# high_side_switch.net
KiCad netlist of a schematic drawn in Altium Designer
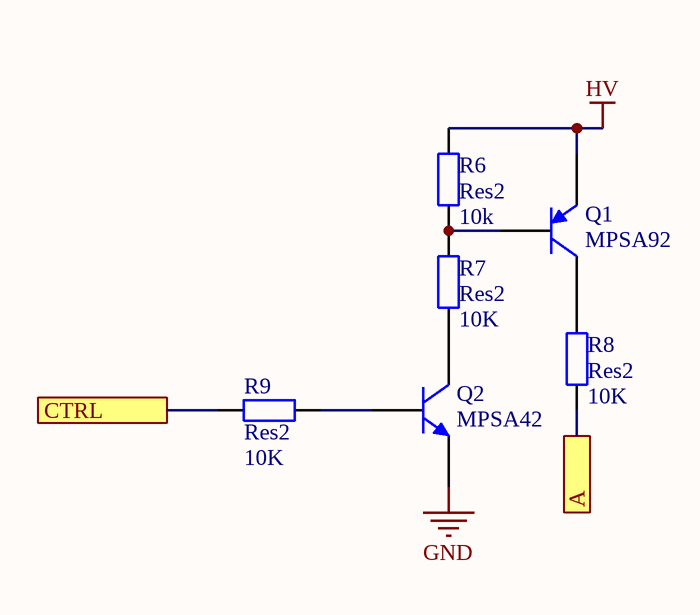
[diagram p0: high_side_switch.SchDoc]

(export (version "E")
  (design (tool "Eeschema 10.0.6"))
  (components
    (comp (ref "Q1")
      (value "MPSA92")
      (footprint "TO-92 bent leads")
      (description "PNP Bipolar Transistor")
      (fields (field (name "PUBLISHER") "Altium Limited"))
      (libsource (lib "Miscellaneous Devices") (part "PNP"))
    )
    (comp (ref "Q2")
      (value "MPSA42")
      (footprint "TO-92 bent leads")
      (description "NPN Bipolar Transistor")
      (fields (field (name "PUBLISHER") "Altium Limited"))
      (libsource (lib "Miscellaneous Devices") (part "NPN"))
    )
    (comp (ref "R6")
      (value "Res2")
      (footprint "0402_res")
      (description "Resistor")
      (fields (field (name "ALTIUM_VALUE") "10k") (field (name "PUBLISHER") "Altium Limited"))
      (libsource (lib "Miscellaneous Devices") (part "Res2"))
    )
    (comp (ref "R7")
      (value "Res2")
      (footprint "0402_res")
      (description "Resistor")
      (fields (field (name "ALTIUM_VALUE") "10K") (field (name "PUBLISHER") "Altium Limited"))
      (libsource (lib "Miscellaneous Devices") (part "Res2"))
    )
    (comp (ref "R8")
      (value "Res2")
      (footprint "0402_res")
      (description "Resistor")
      (fields (field (name "ALTIUM_VALUE") "10K") (field (name "PUBLISHER") "Altium Limited"))
      (libsource (lib "Miscellaneous Devices") (part "Res2"))
    )
    (comp (ref "R9")
      (value "Res2")
      (footprint "0402_res")
      (description "Resistor")
      (fields (field (name "ALTIUM_VALUE") "10K") (field (name "PUBLISHER") "Altium Limited"))
      (libsource (lib "") (part "Res2_1"))
    )
  )
  (nets
    (net (code "1") (name "/A") (class "Default")
      (node (ref "R8") (pin "1") (pinfunction "1_1") (pintype "passive"))
    )
    (net (code "2") (name "/CTRL") (class "Default")
      (node (ref "R9") (pin "2") (pinfunction "2_2") (pintype "passive"))
    )
    (net (code "3") (name "GND") (class "Default")
      (node (ref "Q2") (pin "3") (pinfunction "E_3") (pintype "passive"))
    )
    (net (code "4") (name "HV") (class "Default")
      (node (ref "Q1") (pin "3") (pinfunction "E_3") (pintype "passive"))
      (node (ref "R6") (pin "2") (pinfunction "2_2") (pintype "passive"))
    )
    (net (code "5") (name "Net-(Q1-B)") (class "Default")
      (node (ref "Q1") (pin "2") (pinfunction "B_2") (pintype "passive"))
      (node (ref "R6") (pin "1") (pinfunction "1_1") (pintype "passive"))
      (node (ref "R7") (pin "2") (pinfunction "2_2") (pintype "passive"))
    )
    (net (code "6") (name "Net-(Q1-C)") (class "Default")
      (node (ref "Q1") (pin "1") (pinfunction "C_1") (pintype "passive"))
      (node (ref "R8") (pin "2") (pinfunction "2_2") (pintype "passive"))
    )
    (net (code "7") (name "Net-(Q2-B)") (class "Default")
      (node (ref "Q2") (pin "2") (pinfunction "B_2") (pintype "passive"))
      (node (ref "R9") (pin "1") (pinfunction "1_1") (pintype "passive"))
    )
    (net (code "8") (name "Net-(Q2-C)") (class "Default")
      (node (ref "Q2") (pin "1") (pinfunction "C_1") (pintype "passive"))
      (node (ref "R7") (pin "1") (pinfunction "1_1") (pintype "passive"))
    )
  )
)
